# soundplank.net
KiCad netlist of a schematic drawn in EAGLE
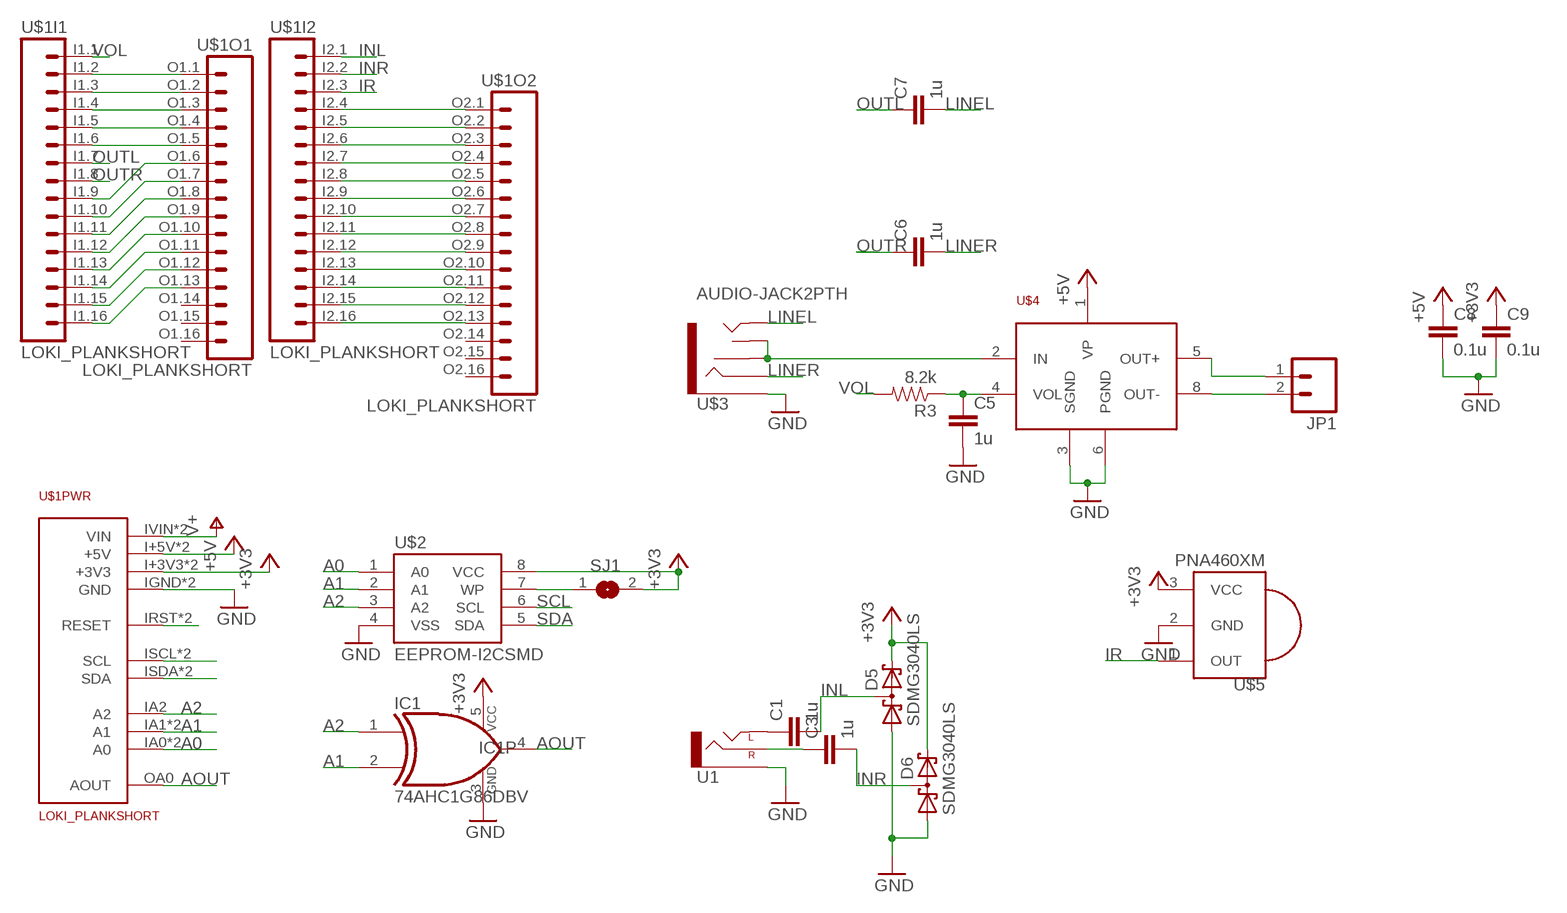
[diagram p0: schematic, sheet 1]

(export (version "E")
  (design (tool "Eeschema 10.0.6"))
  (components
    (comp (ref "C1")
      (value "1u")
      (footprint "eagle-import:1210")
      (libsource (lib "eagle-import") (part "CAP1210"))
    )
    (comp (ref "C3")
      (value "1u")
      (footprint "eagle-import:1210")
      (libsource (lib "eagle-import") (part "CAP1210"))
    )
    (comp (ref "C5")
      (value "1u")
      (footprint "eagle-import:0805")
      (libsource (lib "eagle-import") (part "CAP0805"))
    )
    (comp (ref "C6")
      (value "1u")
      (footprint "eagle-import:1210")
      (libsource (lib "eagle-import") (part "CAP1210"))
    )
    (comp (ref "C7")
      (value "1u")
      (footprint "eagle-import:1210")
      (libsource (lib "eagle-import") (part "CAP1210"))
    )
    (comp (ref "C8")
      (value "0.1u")
      (footprint "eagle-import:0805")
      (libsource (lib "eagle-import") (part "CAP0805"))
    )
    (comp (ref "C9")
      (value "0.1u")
      (footprint "eagle-import:0805")
      (libsource (lib "eagle-import") (part "CAP0805"))
    )
    (comp (ref "D5")
      (value "SDMG3040LS")
      (footprint "eagle-import:SOT23")
      (libsource (lib "eagle-import") (part "BAS40-04"))
    )
    (comp (ref "D6")
      (value "SDMG3040LS")
      (footprint "eagle-import:SOT23")
      (libsource (lib "eagle-import") (part "BAS40-04"))
    )
    (comp (ref "IC1")
      (value "74AHC1G86DBV")
      (footprint "eagle-import:SOT23-5")
      (libsource (lib "eagle-import") (part "741G86DBVAHC"))
    )
    (comp (ref "JP1")
      (value "M023.5MM")
      (footprint "eagle-import:SCREWTERMINAL-3.5MM-2")
      (libsource (lib "eagle-import") (part "M023.5MM"))
    )
    (comp (ref "R3")
      (value "8.2k")
      (footprint "eagle-import:0805")
      (libsource (lib "eagle-import") (part "RESISTOR0805-RES"))
    )
    (comp (ref "SJ1") (value "SJ") (footprint "eagle-import:SJ") (libsource (lib "eagle-import") (part "SJ")))
    (comp (ref "U$1")
      (value "LOKI_PLANKSHORT")
      (footprint "eagle-import:PLANK_SHORT")
      (libsource (lib "eagle-import") (part "LOKI_PLANKSHORT"))
    )
    (comp (ref "U$2")
      (value "EEPROM-I2CSMD")
      (footprint "eagle-import:SO08")
      (libsource (lib "eagle-import") (part "EEPROM-I2CSMD"))
    )
    (comp (ref "U$3")
      (value "AUDIO-JACK2PTH")
      (footprint "eagle-import:AUDIO-JACK")
      (libsource (lib "eagle-import") (part "AUDIO-JACK2PTH"))
    )
    (comp (ref "U$4")
      (value "TDA7052A")
      (footprint "eagle-import:SO08-MAX6675")
      (libsource (lib "eagle-import") (part "TDA7052A"))
    )
    (comp (ref "U$5")
      (value "PNA460XM")
      (footprint "eagle-import:PNA460XM")
      (libsource (lib "eagle-import") (part "PNA460XM"))
    )
    (comp (ref "U1")
      (value "AUDIO-JACKPTH")
      (footprint "eagle-import:AUDIO-JACK")
      (libsource (lib "eagle-import") (part "AUDIO-JACKPTH"))
    )
  )
  (nets
    (net (code "1") (name "+3V3") (class "Default")
      (node (ref "C9") (pin "1") (pinfunction "1_1") (pintype "passive"))
      (node (ref "D5") (pin "2") (pinfunction "C2_2") (pintype "passive"))
      (node (ref "D6") (pin "2") (pinfunction "C2_2") (pintype "passive"))
      (node (ref "IC1") (pin "5") (pinfunction "VCC_5") (pintype "power_in"))
      (node (ref "SJ1") (pin "2") (pinfunction "2_2") (pintype "passive"))
      (node (ref "U$1") (pin "I+3V3") (pinfunction "+3V3_I+3V3") (pintype "power_in"))
      (node (ref "U$1") (pin "O+3V3") (pinfunction "+3V3_O+3V3") (pintype "power_in"))
      (node (ref "U$2") (pin "8") (pinfunction "VCC_8") (pintype "power_in"))
      (node (ref "U$5") (pin "3") (pinfunction "VCC_3") (pintype "power_in"))
    )
    (net (code "2") (name "+5V") (class "Default")
      (node (ref "C8") (pin "1") (pinfunction "1_1") (pintype "passive"))
      (node (ref "U$1") (pin "I+5V") (pinfunction "+5V_I+5V") (pintype "power_in"))
      (node (ref "U$1") (pin "O+5V") (pinfunction "+5V_O+5V") (pintype "power_in"))
      (node (ref "U$4") (pin "1") (pinfunction "VP_1") (pintype "power_in"))
    )
    (net (code "3") (name "/A0") (class "Default")
      (node (ref "U$1") (pin "IA0") (pinfunction "A0_IA0") (pintype "output"))
      (node (ref "U$1") (pin "OA1") (pinfunction "A0_OA1") (pintype "output"))
      (node (ref "U$2") (pin "1") (pinfunction "A0_1") (pintype "bidirectional"))
    )
    (net (code "4") (name "/A1") (class "Default")
      (node (ref "IC1") (pin "2") (pinfunction "I1_2") (pintype "input"))
      (node (ref "U$1") (pin "IA1") (pinfunction "A1_IA1") (pintype "output"))
      (node (ref "U$1") (pin "OA2") (pinfunction "A1_OA2") (pintype "output"))
      (node (ref "U$2") (pin "2") (pinfunction "A1_2") (pintype "bidirectional"))
    )
    (net (code "5") (name "/A2") (class "Default")
      (node (ref "IC1") (pin "1") (pinfunction "I0_1") (pintype "input"))
      (node (ref "U$1") (pin "IA2") (pinfunction "A2_IA2") (pintype "output"))
      (node (ref "U$2") (pin "3") (pinfunction "A2_3") (pintype "bidirectional"))
    )
    (net (code "6") (name "/AOUT") (class "Default")
      (node (ref "IC1") (pin "4") (pinfunction "O_4") (pintype "output"))
      (node (ref "U$1") (pin "OA0") (pinfunction "AOUT_OA0") (pintype "input"))
    )
    (net (code "7") (name "/INL") (class "Default")
      (node (ref "C1") (pin "2") (pinfunction "2_2") (pintype "passive"))
      (node (ref "D5") (pin "3") (pinfunction "C1A2_3") (pintype "passive"))
      (node (ref "U$1") (pin "I2.1") (pinfunction "1_I2.1") (pintype "passive"))
    )
    (net (code "8") (name "/INR") (class "Default")
      (node (ref "C3") (pin "2") (pinfunction "2_2") (pintype "passive"))
      (node (ref "D6") (pin "3") (pinfunction "C1A2_3") (pintype "passive"))
      (node (ref "U$1") (pin "I2.2") (pinfunction "2_I2.2") (pintype "passive"))
    )
    (net (code "9") (name "/IR") (class "Default")
      (node (ref "U$1") (pin "I2.3") (pinfunction "3_I2.3") (pintype "passive"))
      (node (ref "U$5") (pin "1") (pinfunction "OUT_1") (pintype "output"))
    )
    (net (code "10") (name "/LINEL") (class "Default")
      (node (ref "C7") (pin "2") (pinfunction "2_2") (pintype "passive"))
      (node (ref "U$3") (pin "TIP") (pinfunction "TIP_TIP") (pintype "bidirectional"))
    )
    (net (code "11") (name "/LINER") (class "Default")
      (node (ref "C6") (pin "2") (pinfunction "2_2") (pintype "passive"))
      (node (ref "U$3") (pin "RING") (pinfunction "RING_RING") (pintype "bidirectional"))
    )
    (net (code "12") (name "/OUTL") (class "Default")
      (node (ref "C7") (pin "1") (pinfunction "1_1") (pintype "passive"))
      (node (ref "U$1") (pin "I1.7") (pinfunction "7_I1.7") (pintype "passive"))
    )
    (net (code "13") (name "/OUTR") (class "Default")
      (node (ref "C6") (pin "1") (pinfunction "1_1") (pintype "passive"))
      (node (ref "U$1") (pin "I1.8") (pinfunction "8_I1.8") (pintype "passive"))
    )
    (net (code "14") (name "/SCL") (class "Default")
      (node (ref "U$1") (pin "ISCL") (pinfunction "SCL_ISCL") (pintype "bidirectional"))
      (node (ref "U$1") (pin "OSCL") (pinfunction "SCL_OSCL") (pintype "bidirectional"))
      (node (ref "U$2") (pin "6") (pinfunction "SCL_6") (pintype "bidirectional"))
    )
    (net (code "15") (name "/SDA") (class "Default")
      (node (ref "U$1") (pin "ISDA") (pinfunction "SDA_ISDA") (pintype "bidirectional"))
      (node (ref "U$1") (pin "OSDA") (pinfunction "SDA_OSDA") (pintype "bidirectional"))
      (node (ref "U$2") (pin "5") (pinfunction "SDA_5") (pintype "bidirectional"))
    )
    (net (code "16") (name "/VOL") (class "Default")
      (node (ref "R3") (pin "2") (pinfunction "2_2") (pintype "passive"))
      (node (ref "U$1") (pin "I1.1") (pinfunction "1_I1.1") (pintype "passive"))
    )
    (net (code "17") (name "GND") (class "Default")
      (node (ref "C5") (pin "2") (pinfunction "2_2") (pintype "passive"))
      (node (ref "C8") (pin "2") (pinfunction "2_2") (pintype "passive"))
      (node (ref "C9") (pin "2") (pinfunction "2_2") (pintype "passive"))
      (node (ref "D5") (pin "1") (pinfunction "A1_1") (pintype "passive"))
      (node (ref "D6") (pin "1") (pinfunction "A1_1") (pintype "passive"))
      (node (ref "IC1") (pin "3") (pinfunction "GND_3") (pintype "power_in"))
      (node (ref "U$1") (pin "IGND") (pinfunction "GND_IGND") (pintype "power_in"))
      (node (ref "U$1") (pin "OGND") (pinfunction "GND_OGND") (pintype "power_in"))
      (node (ref "U$2") (pin "4") (pinfunction "VSS_4") (pintype "power_in"))
      (node (ref "U$3") (pin "SLEEVE") (pinfunction "SLEEVE_SLEEVE") (pintype "bidirectional"))
      (node (ref "U$4") (pin "3") (pinfunction "SGND_3") (pintype "power_in"))
      (node (ref "U$4") (pin "6") (pinfunction "PGND_6") (pintype "power_in"))
      (node (ref "U$5") (pin "2") (pinfunction "GND_2") (pintype "power_in"))
      (node (ref "U1") (pin "SLEEVE") (pinfunction "SLEEVE_SLEEVE") (pintype "bidirectional"))
    )
    (net (code "18") (name "Net-(U$1A-2)") (class "Default")
      (node (ref "U$1") (pin "I1.2") (pinfunction "2_I1.2") (pintype "passive"))
      (node (ref "U$1") (pin "O1.1") (pinfunction "1_O1.1") (pintype "passive"))
    )
    (net (code "19") (name "Net-(U$1A-3)") (class "Default")
      (node (ref "U$1") (pin "I1.3") (pinfunction "3_I1.3") (pintype "passive"))
      (node (ref "U$1") (pin "O1.2") (pinfunction "2_O1.2") (pintype "passive"))
    )
    (net (code "20") (name "Net-(U$1A-4)") (class "Default")
      (node (ref "U$1") (pin "I1.4") (pinfunction "4_I1.4") (pintype "passive"))
      (node (ref "U$1") (pin "O1.3") (pinfunction "3_O1.3") (pintype "passive"))
    )
    (net (code "21") (name "Net-(U$1A-5)") (class "Default")
      (node (ref "U$1") (pin "I1.5") (pinfunction "5_I1.5") (pintype "passive"))
      (node (ref "U$1") (pin "O1.4") (pinfunction "4_O1.4") (pintype "passive"))
    )
    (net (code "22") (name "Net-(U$1A-6)") (class "Default")
      (node (ref "U$1") (pin "I1.6") (pinfunction "6_I1.6") (pintype "passive"))
      (node (ref "U$1") (pin "O1.5") (pinfunction "5_O1.5") (pintype "passive"))
    )
    (net (code "23") (name "Net-(U$1A-9)") (class "Default")
      (node (ref "U$1") (pin "I1.9") (pinfunction "9_I1.9") (pintype "passive"))
      (node (ref "U$1") (pin "O1.6") (pinfunction "6_O1.6") (pintype "passive"))
    )
    (net (code "24") (name "Net-(U$1A-10)") (class "Default")
      (node (ref "U$1") (pin "I1.10") (pinfunction "10_I1.10") (pintype "passive"))
      (node (ref "U$1") (pin "O1.7") (pinfunction "7_O1.7") (pintype "passive"))
    )
    (net (code "25") (name "Net-(U$1A-11)") (class "Default")
      (node (ref "U$1") (pin "I1.11") (pinfunction "11_I1.11") (pintype "passive"))
      (node (ref "U$1") (pin "O1.8") (pinfunction "8_O1.8") (pintype "passive"))
    )
    (net (code "26") (name "Net-(U$1A-12)") (class "Default")
      (node (ref "U$1") (pin "I1.12") (pinfunction "12_I1.12") (pintype "passive"))
      (node (ref "U$1") (pin "O1.9") (pinfunction "9_O1.9") (pintype "passive"))
    )
    (net (code "27") (name "Net-(U$1A-13)") (class "Default")
      (node (ref "U$1") (pin "I1.13") (pinfunction "13_I1.13") (pintype "passive"))
      (node (ref "U$1") (pin "O1.10") (pinfunction "10_O1.10") (pintype "passive"))
    )
    (net (code "28") (name "Net-(U$1A-14)") (class "Default")
      (node (ref "U$1") (pin "I1.14") (pinfunction "14_I1.14") (pintype "passive"))
      (node (ref "U$1") (pin "O1.11") (pinfunction "11_O1.11") (pintype "passive"))
    )
    (net (code "29") (name "Net-(U$1A-15)") (class "Default")
      (node (ref "U$1") (pin "I1.15") (pinfunction "15_I1.15") (pintype "passive"))
      (node (ref "U$1") (pin "O1.12") (pinfunction "12_O1.12") (pintype "passive"))
    )
    (net (code "30") (name "Net-(U$1A-16)") (class "Default")
      (node (ref "U$1") (pin "I1.16") (pinfunction "16_I1.16") (pintype "passive"))
      (node (ref "U$1") (pin "O1.13") (pinfunction "13_O1.13") (pintype "passive"))
    )
    (net (code "31") (name "Net-(U$1B-4)") (class "Default")
      (node (ref "U$1") (pin "I2.4") (pinfunction "4_I2.4") (pintype "passive"))
      (node (ref "U$1") (pin "O2.1") (pinfunction "1_O2.1") (pintype "passive"))
    )
    (net (code "32") (name "Net-(U$1B-5)") (class "Default")
      (node (ref "U$1") (pin "I2.5") (pinfunction "5_I2.5") (pintype "passive"))
      (node (ref "U$1") (pin "O2.2") (pinfunction "2_O2.2") (pintype "passive"))
    )
    (net (code "33") (name "Net-(U$1B-6)") (class "Default")
      (node (ref "U$1") (pin "I2.6") (pinfunction "6_I2.6") (pintype "passive"))
      (node (ref "U$1") (pin "O2.3") (pinfunction "3_O2.3") (pintype "passive"))
    )
    (net (code "34") (name "Net-(U$1B-7)") (class "Default")
      (node (ref "U$1") (pin "I2.7") (pinfunction "7_I2.7") (pintype "passive"))
      (node (ref "U$1") (pin "O2.4") (pinfunction "4_O2.4") (pintype "passive"))
    )
    (net (code "35") (name "Net-(U$1B-8)") (class "Default")
      (node (ref "U$1") (pin "I2.8") (pinfunction "8_I2.8") (pintype "passive"))
      (node (ref "U$1") (pin "O2.5") (pinfunction "5_O2.5") (pintype "passive"))
    )
    (net (code "36") (name "Net-(U$1B-9)") (class "Default")
      (node (ref "U$1") (pin "I2.9") (pinfunction "9_I2.9") (pintype "passive"))
      (node (ref "U$1") (pin "O2.6") (pinfunction "6_O2.6") (pintype "passive"))
    )
    (net (code "37") (name "Net-(U$1B-10)") (class "Default")
      (node (ref "U$1") (pin "I2.10") (pinfunction "10_I2.10") (pintype "passive"))
      (node (ref "U$1") (pin "O2.7") (pinfunction "7_O2.7") (pintype "passive"))
    )
    (net (code "38") (name "Net-(U$1B-11)") (class "Default")
      (node (ref "U$1") (pin "I2.11") (pinfunction "11_I2.11") (pintype "passive"))
      (node (ref "U$1") (pin "O2.8") (pinfunction "8_O2.8") (pintype "passive"))
    )
    (net (code "39") (name "Net-(U$1B-12)") (class "Default")
      (node (ref "U$1") (pin "I2.12") (pinfunction "12_I2.12") (pintype "passive"))
      (node (ref "U$1") (pin "O2.9") (pinfunction "9_O2.9") (pintype "passive"))
    )
    (net (code "40") (name "Net-(U$1B-13)") (class "Default")
      (node (ref "U$1") (pin "I2.13") (pinfunction "13_I2.13") (pintype "passive"))
      (node (ref "U$1") (pin "O2.10") (pinfunction "10_O2.10") (pintype "passive"))
    )
    (net (code "41") (name "Net-(U$1B-14)") (class "Default")
      (node (ref "U$1") (pin "I2.14") (pinfunction "14_I2.14") (pintype "passive"))
      (node (ref "U$1") (pin "O2.11") (pinfunction "11_O2.11") (pintype "passive"))
    )
    (net (code "42") (name "Net-(U$1B-15)") (class "Default")
      (node (ref "U$1") (pin "I2.15") (pinfunction "15_I2.15") (pintype "passive"))
      (node (ref "U$1") (pin "O2.12") (pinfunction "12_O2.12") (pintype "passive"))
    )
    (net (code "43") (name "Net-(U$1B-16)") (class "Default")
      (node (ref "U$1") (pin "I2.16") (pinfunction "16_I2.16") (pintype "passive"))
      (node (ref "U$1") (pin "O2.13") (pinfunction "13_O2.13") (pintype "passive"))
    )
    (net (code "44") (name "Net-(U$1E-RESET-PadIRST)") (class "Default")
      (node (ref "U$1") (pin "IRST") (pinfunction "RESET_IRST") (pintype "input"))
      (node (ref "U$1") (pin "ORST") (pinfunction "RESET_ORST") (pintype "input"))
    )
    (net (code "45") (name "Net-(U$2-WP)") (class "Default")
      (node (ref "SJ1") (pin "1") (pinfunction "1_1") (pintype "passive"))
      (node (ref "U$2") (pin "7") (pinfunction "WP_7") (pintype "bidirectional"))
    )
    (net (code "46") (name "Net-(U$4-IN)") (class "Default")
      (node (ref "U$3") (pin "RSH") (pinfunction "RSH_RSH") (pintype "bidirectional"))
      (node (ref "U$3") (pin "TSH") (pinfunction "TSH_TSH") (pintype "bidirectional"))
      (node (ref "U$4") (pin "2") (pinfunction "IN_2") (pintype "input"))
    )
    (net (code "47") (name "Net-(U$4-OUT+)") (class "Default")
      (node (ref "JP1") (pin "1") (pinfunction "1_1") (pintype "passive"))
      (node (ref "U$4") (pin "5") (pinfunction "OUT+_5") (pintype "output"))
    )
    (net (code "48") (name "Net-(U$4-OUT-)") (class "Default")
      (node (ref "JP1") (pin "2") (pinfunction "2_2") (pintype "passive"))
      (node (ref "U$4") (pin "8") (pinfunction "OUT-_8") (pintype "output"))
    )
    (net (code "49") (name "Net-(U$4-VOL)") (class "Default")
      (node (ref "C5") (pin "1") (pinfunction "1_1") (pintype "passive"))
      (node (ref "R3") (pin "1") (pinfunction "1_1") (pintype "passive"))
      (node (ref "U$4") (pin "4") (pinfunction "VOL_4") (pintype "input"))
    )
    (net (code "50") (name "Net-(U1-LEFT)") (class "Default")
      (node (ref "C1") (pin "1") (pinfunction "1_1") (pintype "passive"))
      (node (ref "U1") (pin "TIP") (pinfunction "LEFT_TIP") (pintype "bidirectional"))
    )
    (net (code "51") (name "Net-(U1-RIGHT)") (class "Default")
      (node (ref "C3") (pin "1") (pinfunction "1_1") (pintype "passive"))
      (node (ref "U1") (pin "RING") (pinfunction "RIGHT_RING") (pintype "bidirectional"))
    )
    (net (code "52") (name "V+") (class "Default")
      (node (ref "U$1") (pin "IVIN") (pinfunction "VIN_IVIN") (pintype "power_in"))
      (node (ref "U$1") (pin "OVIN") (pinfunction "VIN_OVIN") (pintype "power_in"))
    )
    (net (code "53") (name "unconnected-(U$1C-14-PadO1.14)") (class "Default")
      (node (ref "U$1") (pin "O1.14") (pinfunction "14_O1.14") (pintype "passive"))
    )
    (net (code "54") (name "unconnected-(U$1C-15-PadO1.15)") (class "Default")
      (node (ref "U$1") (pin "O1.15") (pinfunction "15_O1.15") (pintype "passive"))
    )
    (net (code "55") (name "unconnected-(U$1C-16-PadO1.16)") (class "Default")
      (node (ref "U$1") (pin "O1.16") (pinfunction "16_O1.16") (pintype "passive"))
    )
    (net (code "56") (name "unconnected-(U$1D-14-PadO2.14)") (class "Default")
      (node (ref "U$1") (pin "O2.14") (pinfunction "14_O2.14") (pintype "passive"))
    )
    (net (code "57") (name "unconnected-(U$1D-15-PadO2.15)") (class "Default")
      (node (ref "U$1") (pin "O2.15") (pinfunction "15_O2.15") (pintype "passive"))
    )
    (net (code "58") (name "unconnected-(U$1D-16-PadO2.16)") (class "Default")
      (node (ref "U$1") (pin "O2.16") (pinfunction "16_O2.16") (pintype "passive"))
    )
  )
)
